# AD_1.net
KiCad netlist of a schematic drawn in Altium Designer
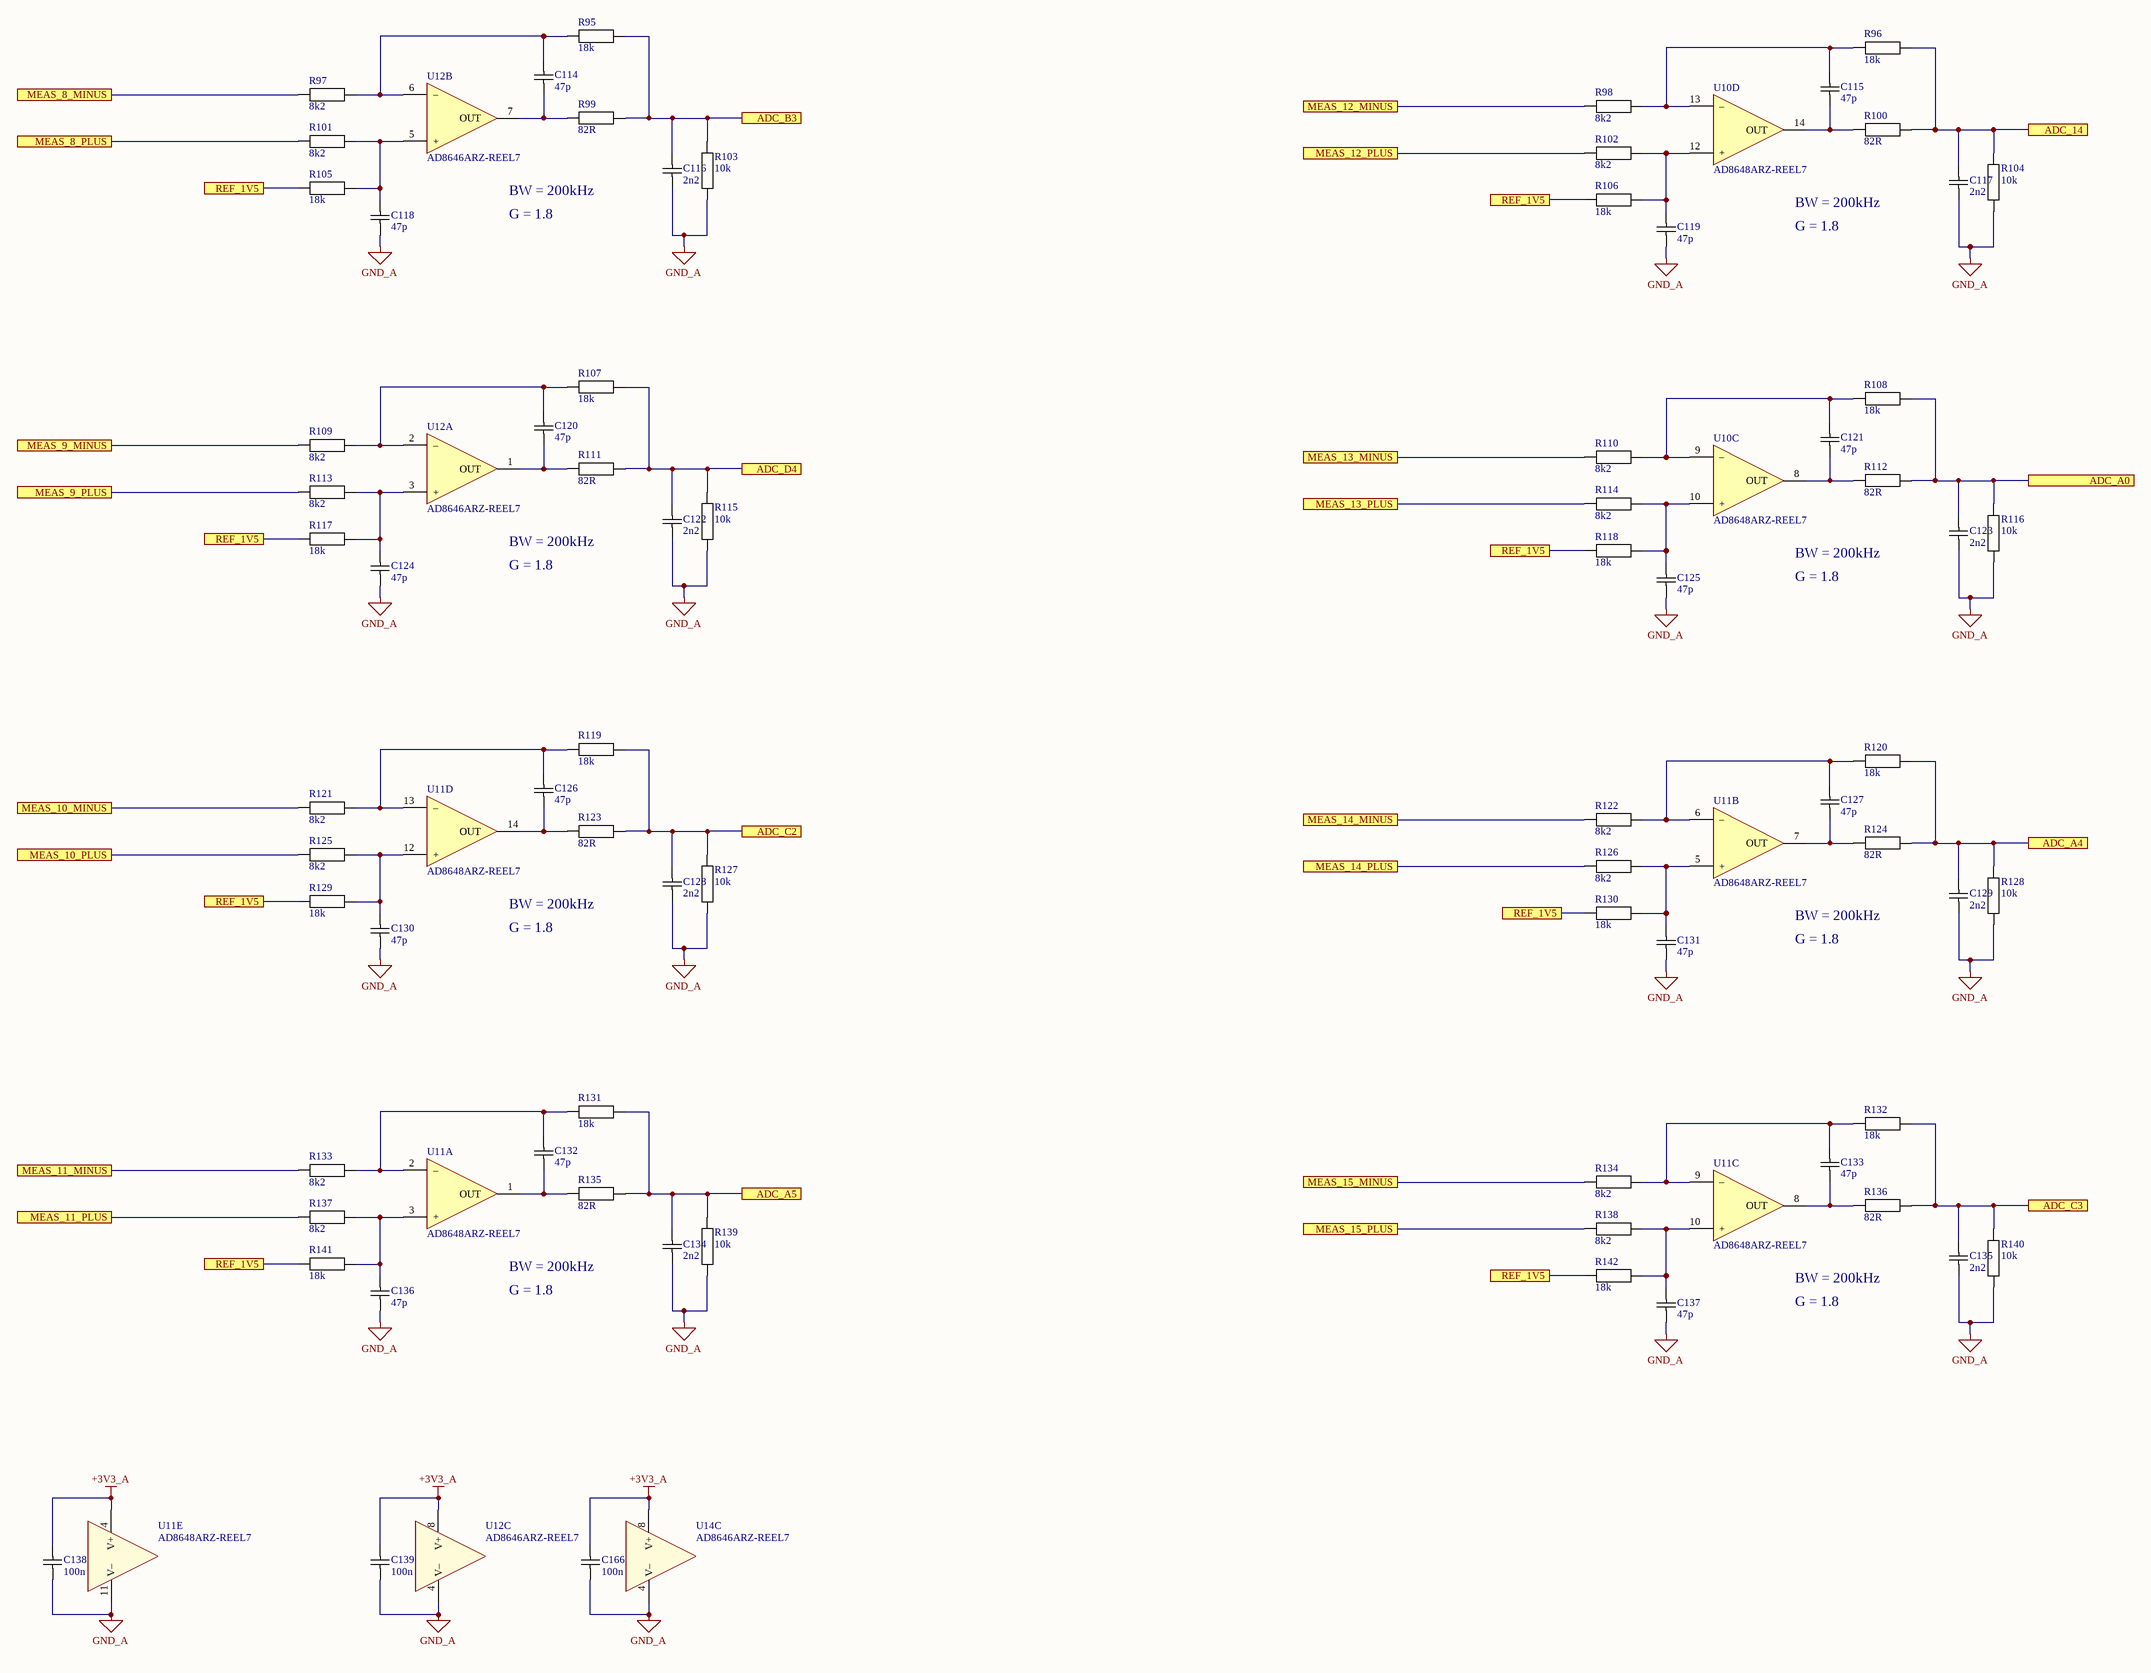
[diagram p0: AD_1.SchDoc]

(export (version "E")
  (design (tool "Eeschema 10.0.6"))
  (components
    (comp (ref "C114")
      (value "47p")
      (footprint "CAPACITOR 1608 REFLOW")
      (description "Capacitor X7R 10% 50V 1608(0603)")
      (libsource (lib "Capacitor") (part "Capacitor"))
    )
    (comp (ref "C115")
      (value "47p")
      (footprint "CAPACITOR 1608 REFLOW")
      (description "Capacitor X7R 10% 50V 1608(0603)")
      (libsource (lib "Capacitor") (part "Capacitor"))
    )
    (comp (ref "C116")
      (value "2n2")
      (footprint "CAPACITOR 1608 REFLOW")
      (description "Capacitor X7R 10% 50V 1608(0603)")
      (libsource (lib "Capacitor") (part "Capacitor"))
    )
    (comp (ref "C117")
      (value "2n2")
      (footprint "CAPACITOR 1608 REFLOW")
      (description "Capacitor X7R 10% 50V 1608(0603)")
      (libsource (lib "Capacitor") (part "Capacitor"))
    )
    (comp (ref "C118")
      (value "47p")
      (footprint "CAPACITOR 1608 REFLOW")
      (description "Capacitor X7R 10% 50V 1608(0603)")
      (libsource (lib "Capacitor") (part "Capacitor"))
    )
    (comp (ref "C119")
      (value "47p")
      (footprint "CAPACITOR 1608 REFLOW")
      (description "Capacitor X7R 10% 50V 1608(0603)")
      (libsource (lib "Capacitor") (part "Capacitor"))
    )
    (comp (ref "C120")
      (value "47p")
      (footprint "CAPACITOR 1608 REFLOW")
      (description "Capacitor X7R 10% 50V 1608(0603)")
      (libsource (lib "Capacitor") (part "Capacitor"))
    )
    (comp (ref "C121")
      (value "47p")
      (footprint "CAPACITOR 1608 REFLOW")
      (description "Capacitor X7R 10% 50V 1608(0603)")
      (libsource (lib "Capacitor") (part "Capacitor"))
    )
    (comp (ref "C122")
      (value "2n2")
      (footprint "CAPACITOR 1608 REFLOW")
      (description "Capacitor X7R 10% 50V 1608(0603)")
      (libsource (lib "Capacitor") (part "Capacitor"))
    )
    (comp (ref "C123")
      (value "2n2")
      (footprint "CAPACITOR 1608 REFLOW")
      (description "Capacitor X7R 10% 50V 1608(0603)")
      (libsource (lib "Capacitor") (part "Capacitor"))
    )
    (comp (ref "C124")
      (value "47p")
      (footprint "CAPACITOR 1608 REFLOW")
      (description "Capacitor X7R 10% 50V 1608(0603)")
      (libsource (lib "Capacitor") (part "Capacitor"))
    )
    (comp (ref "C125")
      (value "47p")
      (footprint "CAPACITOR 1608 REFLOW")
      (description "Capacitor X7R 10% 50V 1608(0603)")
      (libsource (lib "Capacitor") (part "Capacitor"))
    )
    (comp (ref "C126")
      (value "47p")
      (footprint "CAPACITOR 1608 REFLOW")
      (description "Capacitor X7R 10% 50V 1608(0603)")
      (libsource (lib "Capacitor") (part "Capacitor"))
    )
    (comp (ref "C127")
      (value "47p")
      (footprint "CAPACITOR 1608 REFLOW")
      (description "Capacitor X7R 10% 50V 1608(0603)")
      (libsource (lib "Capacitor") (part "Capacitor"))
    )
    (comp (ref "C128")
      (value "2n2")
      (footprint "CAPACITOR 1608 REFLOW")
      (description "Capacitor X7R 10% 50V 1608(0603)")
      (libsource (lib "Capacitor") (part "Capacitor"))
    )
    (comp (ref "C129")
      (value "2n2")
      (footprint "CAPACITOR 1608 REFLOW")
      (description "Capacitor X7R 10% 50V 1608(0603)")
      (libsource (lib "Capacitor") (part "Capacitor"))
    )
    (comp (ref "C130")
      (value "47p")
      (footprint "CAPACITOR 1608 REFLOW")
      (description "Capacitor X7R 10% 50V 1608(0603)")
      (libsource (lib "Capacitor") (part "Capacitor"))
    )
    (comp (ref "C131")
      (value "47p")
      (footprint "CAPACITOR 1608 REFLOW")
      (description "Capacitor X7R 10% 50V 1608(0603)")
      (libsource (lib "Capacitor") (part "Capacitor"))
    )
    (comp (ref "C132")
      (value "47p")
      (footprint "CAPACITOR 1608 REFLOW")
      (description "Capacitor X7R 10% 50V 1608(0603)")
      (libsource (lib "Capacitor") (part "Capacitor"))
    )
    (comp (ref "C133")
      (value "47p")
      (footprint "CAPACITOR 1608 REFLOW")
      (description "Capacitor X7R 10% 50V 1608(0603)")
      (libsource (lib "Capacitor") (part "Capacitor"))
    )
    (comp (ref "C134")
      (value "2n2")
      (footprint "CAPACITOR 1608 REFLOW")
      (description "Capacitor X7R 10% 50V 1608(0603)")
      (libsource (lib "Capacitor") (part "Capacitor"))
    )
    (comp (ref "C135")
      (value "2n2")
      (footprint "CAPACITOR 1608 REFLOW")
      (description "Capacitor X7R 10% 50V 1608(0603)")
      (libsource (lib "Capacitor") (part "Capacitor"))
    )
    (comp (ref "C136")
      (value "47p")
      (footprint "CAPACITOR 1608 REFLOW")
      (description "Capacitor X7R 10% 50V 1608(0603)")
      (libsource (lib "Capacitor") (part "Capacitor"))
    )
    (comp (ref "C137")
      (value "47p")
      (footprint "CAPACITOR 1608 REFLOW")
      (description "Capacitor X7R 10% 50V 1608(0603)")
      (libsource (lib "Capacitor") (part "Capacitor"))
    )
    (comp (ref "C138")
      (value "100n")
      (footprint "CAPACITOR 1608 REFLOW")
      (description "Capacitor X7R 10% 50V 1608(0603)")
      (libsource (lib "Capacitor") (part "Capacitor"))
    )
    (comp (ref "C139")
      (value "100n")
      (footprint "CAPACITOR 1608 REFLOW")
      (description "Capacitor X7R 10% 50V 1608(0603)")
      (libsource (lib "Capacitor") (part "Capacitor"))
    )
    (comp (ref "C166")
      (value "100n")
      (footprint "CAPACITOR 1608 REFLOW")
      (description "Capacitor X7R 10% 50V 1608(0603)")
      (libsource (lib "Capacitor") (part "Capacitor"))
    )
    (comp (ref "R95")
      (value "18k")
      (footprint "RESISTOR 1608 REFLOW")
      (description "Resistor 1% 50V 100mW 1608(0603)")
      (libsource (lib "Resistor") (part "Resistor"))
    )
    (comp (ref "R96")
      (value "18k")
      (footprint "RESISTOR 1608 REFLOW")
      (description "Resistor 1% 50V 100mW 1608(0603)")
      (libsource (lib "Resistor") (part "Resistor"))
    )
    (comp (ref "R97")
      (value "8k2")
      (footprint "RESISTOR 1608 REFLOW")
      (description "Resistor 1% 50V 100mW 1608(0603)")
      (libsource (lib "Resistor") (part "Resistor"))
    )
    (comp (ref "R98")
      (value "8k2")
      (footprint "RESISTOR 1608 REFLOW")
      (description "Resistor 1% 50V 100mW 1608(0603)")
      (libsource (lib "Resistor") (part "Resistor"))
    )
    (comp (ref "R99")
      (value "82R")
      (footprint "RESISTOR 1608 REFLOW")
      (description "Resistor 1% 50V 100mW 1608(0603)")
      (libsource (lib "Resistor") (part "Resistor"))
    )
    (comp (ref "R100")
      (value "82R")
      (footprint "RESISTOR 1608 REFLOW")
      (description "Resistor 1% 50V 100mW 1608(0603)")
      (libsource (lib "Resistor") (part "Resistor"))
    )
    (comp (ref "R101")
      (value "8k2")
      (footprint "RESISTOR 1608 REFLOW")
      (description "Resistor 1% 50V 100mW 1608(0603)")
      (libsource (lib "Resistor") (part "Resistor"))
    )
    (comp (ref "R102")
      (value "8k2")
      (footprint "RESISTOR 1608 REFLOW")
      (description "Resistor 1% 50V 100mW 1608(0603)")
      (libsource (lib "Resistor") (part "Resistor"))
    )
    (comp (ref "R103")
      (value "10k")
      (footprint "RESISTOR 1608 REFLOW")
      (description "Resistor 1% 50V 100mW 1608(0603)")
      (libsource (lib "Resistor") (part "Resistor"))
    )
    (comp (ref "R104")
      (value "10k")
      (footprint "RESISTOR 1608 REFLOW")
      (description "Resistor 1% 50V 100mW 1608(0603)")
      (libsource (lib "Resistor") (part "Resistor"))
    )
    (comp (ref "R105")
      (value "18k")
      (footprint "RESISTOR 1608 REFLOW")
      (description "Resistor 1% 50V 100mW 1608(0603)")
      (libsource (lib "Resistor") (part "Resistor"))
    )
    (comp (ref "R106")
      (value "18k")
      (footprint "RESISTOR 1608 REFLOW")
      (description "Resistor 1% 50V 100mW 1608(0603)")
      (libsource (lib "Resistor") (part "Resistor"))
    )
    (comp (ref "R107")
      (value "18k")
      (footprint "RESISTOR 1608 REFLOW")
      (description "Resistor 1% 50V 100mW 1608(0603)")
      (libsource (lib "Resistor") (part "Resistor"))
    )
    (comp (ref "R108")
      (value "18k")
      (footprint "RESISTOR 1608 REFLOW")
      (description "Resistor 1% 50V 100mW 1608(0603)")
      (libsource (lib "Resistor") (part "Resistor"))
    )
    (comp (ref "R109")
      (value "8k2")
      (footprint "RESISTOR 1608 REFLOW")
      (description "Resistor 1% 50V 100mW 1608(0603)")
      (libsource (lib "Resistor") (part "Resistor"))
    )
    (comp (ref "R110")
      (value "8k2")
      (footprint "RESISTOR 1608 REFLOW")
      (description "Resistor 1% 50V 100mW 1608(0603)")
      (libsource (lib "Resistor") (part "Resistor"))
    )
    (comp (ref "R111")
      (value "82R")
      (footprint "RESISTOR 1608 REFLOW")
      (description "Resistor 1% 50V 100mW 1608(0603)")
      (libsource (lib "Resistor") (part "Resistor"))
    )
    (comp (ref "R112")
      (value "82R")
      (footprint "RESISTOR 1608 REFLOW")
      (description "Resistor 1% 50V 100mW 1608(0603)")
      (libsource (lib "Resistor") (part "Resistor"))
    )
    (comp (ref "R113")
      (value "8k2")
      (footprint "RESISTOR 1608 REFLOW")
      (description "Resistor 1% 50V 100mW 1608(0603)")
      (libsource (lib "Resistor") (part "Resistor"))
    )
    (comp (ref "R114")
      (value "8k2")
      (footprint "RESISTOR 1608 REFLOW")
      (description "Resistor 1% 50V 100mW 1608(0603)")
      (libsource (lib "Resistor") (part "Resistor"))
    )
    (comp (ref "R115")
      (value "10k")
      (footprint "RESISTOR 1608 REFLOW")
      (description "Resistor 1% 50V 100mW 1608(0603)")
      (libsource (lib "Resistor") (part "Resistor"))
    )
    (comp (ref "R116")
      (value "10k")
      (footprint "RESISTOR 1608 REFLOW")
      (description "Resistor 1% 50V 100mW 1608(0603)")
      (libsource (lib "Resistor") (part "Resistor"))
    )
    (comp (ref "R117")
      (value "18k")
      (footprint "RESISTOR 1608 REFLOW")
      (description "Resistor 1% 50V 100mW 1608(0603)")
      (libsource (lib "Resistor") (part "Resistor"))
    )
    (comp (ref "R118")
      (value "18k")
      (footprint "RESISTOR 1608 REFLOW")
      (description "Resistor 1% 50V 100mW 1608(0603)")
      (libsource (lib "Resistor") (part "Resistor"))
    )
    (comp (ref "R119")
      (value "18k")
      (footprint "RESISTOR 1608 REFLOW")
      (description "Resistor 1% 50V 100mW 1608(0603)")
      (libsource (lib "Resistor") (part "Resistor"))
    )
    (comp (ref "R120")
      (value "18k")
      (footprint "RESISTOR 1608 REFLOW")
      (description "Resistor 1% 50V 100mW 1608(0603)")
      (libsource (lib "Resistor") (part "Resistor"))
    )
    (comp (ref "R121")
      (value "8k2")
      (footprint "RESISTOR 1608 REFLOW")
      (description "Resistor 1% 50V 100mW 1608(0603)")
      (libsource (lib "Resistor") (part "Resistor"))
    )
    (comp (ref "R122")
      (value "8k2")
      (footprint "RESISTOR 1608 REFLOW")
      (description "Resistor 1% 50V 100mW 1608(0603)")
      (libsource (lib "Resistor") (part "Resistor"))
    )
    (comp (ref "R123")
      (value "82R")
      (footprint "RESISTOR 1608 REFLOW")
      (description "Resistor 1% 50V 100mW 1608(0603)")
      (libsource (lib "Resistor") (part "Resistor"))
    )
    (comp (ref "R124")
      (value "82R")
      (footprint "RESISTOR 1608 REFLOW")
      (description "Resistor 1% 50V 100mW 1608(0603)")
      (libsource (lib "Resistor") (part "Resistor"))
    )
    (comp (ref "R125")
      (value "8k2")
      (footprint "RESISTOR 1608 REFLOW")
      (description "Resistor 1% 50V 100mW 1608(0603)")
      (libsource (lib "Resistor") (part "Resistor"))
    )
    (comp (ref "R126")
      (value "8k2")
      (footprint "RESISTOR 1608 REFLOW")
      (description "Resistor 1% 50V 100mW 1608(0603)")
      (libsource (lib "Resistor") (part "Resistor"))
    )
    (comp (ref "R127")
      (value "10k")
      (footprint "RESISTOR 1608 REFLOW")
      (description "Resistor 1% 50V 100mW 1608(0603)")
      (libsource (lib "Resistor") (part "Resistor"))
    )
    (comp (ref "R128")
      (value "10k")
      (footprint "RESISTOR 1608 REFLOW")
      (description "Resistor 1% 50V 100mW 1608(0603)")
      (libsource (lib "Resistor") (part "Resistor"))
    )
    (comp (ref "R129")
      (value "18k")
      (footprint "RESISTOR 1608 REFLOW")
      (description "Resistor 1% 50V 100mW 1608(0603)")
      (libsource (lib "Resistor") (part "Resistor"))
    )
    (comp (ref "R130")
      (value "18k")
      (footprint "RESISTOR 1608 REFLOW")
      (description "Resistor 1% 50V 100mW 1608(0603)")
      (libsource (lib "Resistor") (part "Resistor"))
    )
    (comp (ref "R131")
      (value "18k")
      (footprint "RESISTOR 1608 REFLOW")
      (description "Resistor 1% 50V 100mW 1608(0603)")
      (libsource (lib "Resistor") (part "Resistor"))
    )
    (comp (ref "R132")
      (value "18k")
      (footprint "RESISTOR 1608 REFLOW")
      (description "Resistor 1% 50V 100mW 1608(0603)")
      (libsource (lib "Resistor") (part "Resistor"))
    )
    (comp (ref "R133")
      (value "8k2")
      (footprint "RESISTOR 1608 REFLOW")
      (description "Resistor 1% 50V 100mW 1608(0603)")
      (libsource (lib "Resistor") (part "Resistor"))
    )
    (comp (ref "R134")
      (value "8k2")
      (footprint "RESISTOR 1608 REFLOW")
      (description "Resistor 1% 50V 100mW 1608(0603)")
      (libsource (lib "Resistor") (part "Resistor"))
    )
    (comp (ref "R135")
      (value "82R")
      (footprint "RESISTOR 1608 REFLOW")
      (description "Resistor 1% 50V 100mW 1608(0603)")
      (libsource (lib "Resistor") (part "Resistor"))
    )
    (comp (ref "R136")
      (value "82R")
      (footprint "RESISTOR 1608 REFLOW")
      (description "Resistor 1% 50V 100mW 1608(0603)")
      (libsource (lib "Resistor") (part "Resistor"))
    )
    (comp (ref "R137")
      (value "8k2")
      (footprint "RESISTOR 1608 REFLOW")
      (description "Resistor 1% 50V 100mW 1608(0603)")
      (libsource (lib "Resistor") (part "Resistor"))
    )
    (comp (ref "R138")
      (value "8k2")
      (footprint "RESISTOR 1608 REFLOW")
      (description "Resistor 1% 50V 100mW 1608(0603)")
      (libsource (lib "Resistor") (part "Resistor"))
    )
    (comp (ref "R139")
      (value "10k")
      (footprint "RESISTOR 1608 REFLOW")
      (description "Resistor 1% 50V 100mW 1608(0603)")
      (libsource (lib "Resistor") (part "Resistor"))
    )
    (comp (ref "R140")
      (value "10k")
      (footprint "RESISTOR 1608 REFLOW")
      (description "Resistor 1% 50V 100mW 1608(0603)")
      (libsource (lib "Resistor") (part "Resistor"))
    )
    (comp (ref "R141")
      (value "18k")
      (footprint "RESISTOR 1608 REFLOW")
      (description "Resistor 1% 50V 100mW 1608(0603)")
      (libsource (lib "Resistor") (part "Resistor"))
    )
    (comp (ref "R142")
      (value "18k")
      (footprint "RESISTOR 1608 REFLOW")
      (description "Resistor 1% 50V 100mW 1608(0603)")
      (libsource (lib "Resistor") (part "Resistor"))
    )
    (comp (ref "U10")
      (value "AD8648ARZ-REEL7")
      (footprint "SO14 P1.27 C4.0X8.8 H1.75")
      (description "Generic quad OPA 14 pins")
      (fields (field (name "MANUFACTURER") "Analog Devices"))
      (libsource (lib "Amplifier") (part "OPA QUAD"))
    )
    (comp (ref "U11")
      (value "AD8648ARZ-REEL7")
      (footprint "SO14 P1.27 C4.0X8.8 H1.75")
      (description "Generic quad OPA 14 pins")
      (fields (field (name "MANUFACTURER") "Analog Devices"))
      (libsource (lib "Amplifier") (part "OPA QUAD"))
    )
    (comp (ref "U12")
      (value "AD8646ARZ-REEL7")
      (footprint "SO8 P1.27 C4.0X5.0 H1.75")
      (description "Generic dual OPA 8 pins")
      (fields (field (name "MANUFACTURER") "Analog Devices"))
      (libsource (lib "Amplifier") (part "OPA DUAL"))
    )
    (comp (ref "U14")
      (value "AD8646ARZ-REEL7")
      (footprint "SO8 P1.27 C4.0X5.0 H1.75")
      (description "Generic dual OPA 8 pins")
      (fields (field (name "MANUFACTURER") "Analog Devices"))
      (libsource (lib "Amplifier") (part "OPA DUAL"))
    )
  )
  (nets
    (net (code "1") (name "+3V3_A") (class "Default")
      (node (ref "C138") (pin "2") (pinfunction "2_2") (pintype "passive"))
      (node (ref "C139") (pin "2") (pinfunction "2_2") (pintype "passive"))
      (node (ref "C166") (pin "2") (pinfunction "2_2") (pintype "passive"))
      (node (ref "U11") (pin "4") (pinfunction "V+_4") (pintype "passive"))
      (node (ref "U12") (pin "8") (pinfunction "V+_8") (pintype "passive"))
      (node (ref "U14") (pin "8") (pinfunction "V+_8") (pintype "passive"))
    )
    (net (code "2") (name "/ADC_14") (class "Default")
      (node (ref "C117") (pin "2") (pinfunction "2_2") (pintype "passive"))
      (node (ref "R100") (pin "2") (pinfunction "2_2") (pintype "passive"))
      (node (ref "R104") (pin "1") (pinfunction "1_1") (pintype "passive"))
      (node (ref "R96") (pin "2") (pinfunction "2_2") (pintype "passive"))
    )
    (net (code "3") (name "/ADC_A0") (class "Default")
      (node (ref "C123") (pin "2") (pinfunction "2_2") (pintype "passive"))
      (node (ref "R108") (pin "2") (pinfunction "2_2") (pintype "passive"))
      (node (ref "R112") (pin "2") (pinfunction "2_2") (pintype "passive"))
      (node (ref "R116") (pin "1") (pinfunction "1_1") (pintype "passive"))
    )
    (net (code "4") (name "/ADC_A4") (class "Default")
      (node (ref "C129") (pin "2") (pinfunction "2_2") (pintype "passive"))
      (node (ref "R120") (pin "2") (pinfunction "2_2") (pintype "passive"))
      (node (ref "R124") (pin "2") (pinfunction "2_2") (pintype "passive"))
      (node (ref "R128") (pin "1") (pinfunction "1_1") (pintype "passive"))
    )
    (net (code "5") (name "/ADC_A5") (class "Default")
      (node (ref "C134") (pin "2") (pinfunction "2_2") (pintype "passive"))
      (node (ref "R131") (pin "2") (pinfunction "2_2") (pintype "passive"))
      (node (ref "R135") (pin "2") (pinfunction "2_2") (pintype "passive"))
      (node (ref "R139") (pin "1") (pinfunction "1_1") (pintype "passive"))
    )
    (net (code "6") (name "/ADC_B3") (class "Default")
      (node (ref "C116") (pin "2") (pinfunction "2_2") (pintype "passive"))
      (node (ref "R103") (pin "1") (pinfunction "1_1") (pintype "passive"))
      (node (ref "R95") (pin "2") (pinfunction "2_2") (pintype "passive"))
      (node (ref "R99") (pin "2") (pinfunction "2_2") (pintype "passive"))
    )
    (net (code "7") (name "/ADC_C2") (class "Default")
      (node (ref "C128") (pin "2") (pinfunction "2_2") (pintype "passive"))
      (node (ref "R119") (pin "2") (pinfunction "2_2") (pintype "passive"))
      (node (ref "R123") (pin "2") (pinfunction "2_2") (pintype "passive"))
      (node (ref "R127") (pin "1") (pinfunction "1_1") (pintype "passive"))
    )
    (net (code "8") (name "/ADC_C3") (class "Default")
      (node (ref "C135") (pin "2") (pinfunction "2_2") (pintype "passive"))
      (node (ref "R132") (pin "2") (pinfunction "2_2") (pintype "passive"))
      (node (ref "R136") (pin "2") (pinfunction "2_2") (pintype "passive"))
      (node (ref "R140") (pin "1") (pinfunction "1_1") (pintype "passive"))
    )
    (net (code "9") (name "/ADC_D4") (class "Default")
      (node (ref "C122") (pin "2") (pinfunction "2_2") (pintype "passive"))
      (node (ref "R107") (pin "2") (pinfunction "2_2") (pintype "passive"))
      (node (ref "R111") (pin "2") (pinfunction "2_2") (pintype "passive"))
      (node (ref "R115") (pin "1") (pinfunction "1_1") (pintype "passive"))
    )
    (net (code "10") (name "/MEAS_8_MINUS") (class "Default")
      (node (ref "R97") (pin "1") (pinfunction "1_1") (pintype "passive"))
    )
    (net (code "11") (name "/MEAS_8_PLUS") (class "Default")
      (node (ref "R101") (pin "1") (pinfunction "1_1") (pintype "passive"))
    )
    (net (code "12") (name "/MEAS_9_MINUS") (class "Default")
      (node (ref "R109") (pin "1") (pinfunction "1_1") (pintype "passive"))
    )
    (net (code "13") (name "/MEAS_9_PLUS") (class "Default")
      (node (ref "R113") (pin "1") (pinfunction "1_1") (pintype "passive"))
    )
    (net (code "14") (name "/MEAS_10_MINUS") (class "Default")
      (node (ref "R121") (pin "1") (pinfunction "1_1") (pintype "passive"))
    )
    (net (code "15") (name "/MEAS_10_PLUS") (class "Default")
      (node (ref "R125") (pin "1") (pinfunction "1_1") (pintype "passive"))
    )
    (net (code "16") (name "/MEAS_11_MINUS") (class "Default")
      (node (ref "R133") (pin "1") (pinfunction "1_1") (pintype "passive"))
    )
    (net (code "17") (name "/MEAS_11_PLUS") (class "Default")
      (node (ref "R137") (pin "1") (pinfunction "1_1") (pintype "passive"))
    )
    (net (code "18") (name "/MEAS_12_MINUS") (class "Default")
      (node (ref "R98") (pin "1") (pinfunction "1_1") (pintype "passive"))
    )
    (net (code "19") (name "/MEAS_12_PLUS") (class "Default")
      (node (ref "R102") (pin "1") (pinfunction "1_1") (pintype "passive"))
    )
    (net (code "20") (name "/MEAS_13_MINUS") (class "Default")
      (node (ref "R110") (pin "1") (pinfunction "1_1") (pintype "passive"))
    )
    (net (code "21") (name "/MEAS_13_PLUS") (class "Default")
      (node (ref "R114") (pin "1") (pinfunction "1_1") (pintype "passive"))
    )
    (net (code "22") (name "/MEAS_14_MINUS") (class "Default")
      (node (ref "R122") (pin "1") (pinfunction "1_1") (pintype "passive"))
    )
    (net (code "23") (name "/MEAS_14_PLUS") (class "Default")
      (node (ref "R126") (pin "1") (pinfunction "1_1") (pintype "passive"))
    )
    (net (code "24") (name "/MEAS_15_MINUS") (class "Default")
      (node (ref "R134") (pin "1") (pinfunction "1_1") (pintype "passive"))
    )
    (net (code "25") (name "/MEAS_15_PLUS") (class "Default")
      (node (ref "R138") (pin "1") (pinfunction "1_1") (pintype "passive"))
    )
    (net (code "26") (name "/REF_1V5") (class "Default")
      (node (ref "R105") (pin "2") (pinfunction "2_2") (pintype "passive"))
      (node (ref "R106") (pin "2") (pinfunction "2_2") (pintype "passive"))
      (node (ref "R117") (pin "2") (pinfunction "2_2") (pintype "passive"))
      (node (ref "R118") (pin "2") (pinfunction "2_2") (pintype "passive"))
      (node (ref "R129") (pin "2") (pinfunction "2_2") (pintype "passive"))
      (node (ref "R130") (pin "2") (pinfunction "2_2") (pintype "passive"))
      (node (ref "R141") (pin "2") (pinfunction "2_2") (pintype "passive"))
      (node (ref "R142") (pin "2") (pinfunction "2_2") (pintype "passive"))
    )
    (net (code "27") (name "GND_A") (class "Default")
      (node (ref "C116") (pin "1") (pinfunction "1_1") (pintype "passive"))
      (node (ref "C117") (pin "1") (pinfunction "1_1") (pintype "passive"))
      (node (ref "C118") (pin "1") (pinfunction "1_1") (pintype "passive"))
      (node (ref "C119") (pin "1") (pinfunction "1_1") (pintype "passive"))
      (node (ref "C122") (pin "1") (pinfunction "1_1") (pintype "passive"))
      (node (ref "C123") (pin "1") (pinfunction "1_1") (pintype "passive"))
      (node (ref "C124") (pin "1") (pinfunction "1_1") (pintype "passive"))
      (node (ref "C125") (pin "1") (pinfunction "1_1") (pintype "passive"))
      (node (ref "C128") (pin "1") (pinfunction "1_1") (pintype "passive"))
      (node (ref "C129") (pin "1") (pinfunction "1_1") (pintype "passive"))
      (node (ref "C130") (pin "1") (pinfunction "1_1") (pintype "passive"))
      (node (ref "C131") (pin "1") (pinfunction "1_1") (pintype "passive"))
      (node (ref "C134") (pin "1") (pinfunction "1_1") (pintype "passive"))
      (node (ref "C135") (pin "1") (pinfunction "1_1") (pintype "passive"))
      (node (ref "C136") (pin "1") (pinfunction "1_1") (pintype "passive"))
      (node (ref "C137") (pin "1") (pinfunction "1_1") (pintype "passive"))
      (node (ref "C138") (pin "1") (pinfunction "1_1") (pintype "passive"))
      (node (ref "C139") (pin "1") (pinfunction "1_1") (pintype "passive"))
      (node (ref "C166") (pin "1") (pinfunction "1_1") (pintype "passive"))
      (node (ref "R103") (pin "2") (pinfunction "2_2") (pintype "passive"))
      (node (ref "R104") (pin "2") (pinfunction "2_2") (pintype "passive"))
      (node (ref "R115") (pin "2") (pinfunction "2_2") (pintype "passive"))
      (node (ref "R116") (pin "2") (pinfunction "2_2") (pintype "passive"))
      (node (ref "R127") (pin "2") (pinfunction "2_2") (pintype "passive"))
      (node (ref "R128") (pin "2") (pinfunction "2_2") (pintype "passive"))
      (node (ref "R139") (pin "2") (pinfunction "2_2") (pintype "passive"))
      (node (ref "R140") (pin "2") (pinfunction "2_2") (pintype "passive"))
      (node (ref "U11") (pin "11") (pinfunction "V–_11") (pintype "passive"))
      (node (ref "U12") (pin "4") (pinfunction "V–_4") (pintype "passive"))
      (node (ref "U14") (pin "4") (pinfunction "V–_4") (pintype "passive"))
    )
    (net (code "28") (name "Net-(U10C-+)") (class "Default")
      (node (ref "C125") (pin "2") (pinfunction "2_2") (pintype "passive"))
      (node (ref "R114") (pin "2") (pinfunction "2_2") (pintype "passive"))
      (node (ref "R118") (pin "1") (pinfunction "1_1") (pintype "passive"))
      (node (ref "U10") (pin "10") (pinfunction "+_10") (pintype "passive"))
    )
    (net (code "29") (name "Net-(U10C-OUT)") (class "Default")
      (node (ref "C121") (pin "1") (pinfunction "1_1") (pintype "passive"))
      (node (ref "R112") (pin "1") (pinfunction "1_1") (pintype "passive"))
      (node (ref "U10") (pin "8") (pinfunction "OUT_8") (pintype "passive"))
    )
    (net (code "30") (name "Net-(U10C-–)") (class "Default")
      (node (ref "C121") (pin "2") (pinfunction "2_2") (pintype "passive"))
      (node (ref "R108") (pin "1") (pinfunction "1_1") (pintype "passive"))
      (node (ref "R110") (pin "2") (pinfunction "2_2") (pintype "passive"))
      (node (ref "U10") (pin "9") (pinfunction "–_9") (pintype "passive"))
    )
    (net (code "31") (name "Net-(U10D-+)") (class "Default")
      (node (ref "C119") (pin "2") (pinfunction "2_2") (pintype "passive"))
      (node (ref "R102") (pin "2") (pinfunction "2_2") (pintype "passive"))
      (node (ref "R106") (pin "1") (pinfunction "1_1") (pintype "passive"))
      (node (ref "U10") (pin "12") (pinfunction "+_12") (pintype "passive"))
    )
    (net (code "32") (name "Net-(U10D-OUT)") (class "Default")
      (node (ref "C115") (pin "1") (pinfunction "1_1") (pintype "passive"))
      (node (ref "R100") (pin "1") (pinfunction "1_1") (pintype "passive"))
      (node (ref "U10") (pin "14") (pinfunction "OUT_14") (pintype "passive"))
    )
    (net (code "33") (name "Net-(U10D-–)") (class "Default")
      (node (ref "C115") (pin "2") (pinfunction "2_2") (pintype "passive"))
      (node (ref "R96") (pin "1") (pinfunction "1_1") (pintype "passive"))
      (node (ref "R98") (pin "2") (pinfunction "2_2") (pintype "passive"))
      (node (ref "U10") (pin "13") (pinfunction "–_13") (pintype "passive"))
    )
    (net (code "34") (name "Net-(U11A-+)") (class "Default")
      (node (ref "C136") (pin "2") (pinfunction "2_2") (pintype "passive"))
      (node (ref "R137") (pin "2") (pinfunction "2_2") (pintype "passive"))
      (node (ref "R141") (pin "1") (pinfunction "1_1") (pintype "passive"))
      (node (ref "U11") (pin "3") (pinfunction "+_3") (pintype "passive"))
    )
    (net (code "35") (name "Net-(U11A-OUT)") (class "Default")
      (node (ref "C132") (pin "1") (pinfunction "1_1") (pintype "passive"))
      (node (ref "R135") (pin "1") (pinfunction "1_1") (pintype "passive"))
      (node (ref "U11") (pin "1") (pinfunction "OUT_1") (pintype "passive"))
    )
    (net (code "36") (name "Net-(U11A-–)") (class "Default")
      (node (ref "C132") (pin "2") (pinfunction "2_2") (pintype "passive"))
      (node (ref "R131") (pin "1") (pinfunction "1_1") (pintype "passive"))
      (node (ref "R133") (pin "2") (pinfunction "2_2") (pintype "passive"))
      (node (ref "U11") (pin "2") (pinfunction "–_2") (pintype "passive"))
    )
    (net (code "37") (name "Net-(U11B-+)") (class "Default")
      (node (ref "C131") (pin "2") (pinfunction "2_2") (pintype "passive"))
      (node (ref "R126") (pin "2") (pinfunction "2_2") (pintype "passive"))
      (node (ref "R130") (pin "1") (pinfunction "1_1") (pintype "passive"))
      (node (ref "U11") (pin "5") (pinfunction "+_5") (pintype "passive"))
    )
    (net (code "38") (name "Net-(U11B-OUT)") (class "Default")
      (node (ref "C127") (pin "1") (pinfunction "1_1") (pintype "passive"))
      (node (ref "R124") (pin "1") (pinfunction "1_1") (pintype "passive"))
      (node (ref "U11") (pin "7") (pinfunction "OUT_7") (pintype "passive"))
    )
    (net (code "39") (name "Net-(U11B-–)") (class "Default")
      (node (ref "C127") (pin "2") (pinfunction "2_2") (pintype "passive"))
      (node (ref "R120") (pin "1") (pinfunction "1_1") (pintype "passive"))
      (node (ref "R122") (pin "2") (pinfunction "2_2") (pintype "passive"))
      (node (ref "U11") (pin "6") (pinfunction "–_6") (pintype "passive"))
    )
    (net (code "40") (name "Net-(U11C-+)") (class "Default")
      (node (ref "C137") (pin "2") (pinfunction "2_2") (pintype "passive"))
      (node (ref "R138") (pin "2") (pinfunction "2_2") (pintype "passive"))
      (node (ref "R142") (pin "1") (pinfunction "1_1") (pintype "passive"))
      (node (ref "U11") (pin "10") (pinfunction "+_10") (pintype "passive"))
    )
    (net (code "41") (name "Net-(U11C-OUT)") (class "Default")
      (node (ref "C133") (pin "1") (pinfunction "1_1") (pintype "passive"))
      (node (ref "R136") (pin "1") (pinfunction "1_1") (pintype "passive"))
      (node (ref "U11") (pin "8") (pinfunction "OUT_8") (pintype "passive"))
    )
    (net (code "42") (name "Net-(U11C-–)") (class "Default")
      (node (ref "C133") (pin "2") (pinfunction "2_2") (pintype "passive"))
      (node (ref "R132") (pin "1") (pinfunction "1_1") (pintype "passive"))
      (node (ref "R134") (pin "2") (pinfunction "2_2") (pintype "passive"))
      (node (ref "U11") (pin "9") (pinfunction "–_9") (pintype "passive"))
    )
    (net (code "43") (name "Net-(U11D-+)") (class "Default")
      (node (ref "C130") (pin "2") (pinfunction "2_2") (pintype "passive"))
      (node (ref "R125") (pin "2") (pinfunction "2_2") (pintype "passive"))
      (node (ref "R129") (pin "1") (pinfunction "1_1") (pintype "passive"))
      (node (ref "U11") (pin "12") (pinfunction "+_12") (pintype "passive"))
    )
    (net (code "44") (name "Net-(U11D-OUT)") (class "Default")
      (node (ref "C126") (pin "1") (pinfunction "1_1") (pintype "passive"))
      (node (ref "R123") (pin "1") (pinfunction "1_1") (pintype "passive"))
      (node (ref "U11") (pin "14") (pinfunction "OUT_14") (pintype "passive"))
    )
    (net (code "45") (name "Net-(U11D-–)") (class "Default")
      (node (ref "C126") (pin "2") (pinfunction "2_2") (pintype "passive"))
      (node (ref "R119") (pin "1") (pinfunction "1_1") (pintype "passive"))
      (node (ref "R121") (pin "2") (pinfunction "2_2") (pintype "passive"))
      (node (ref "U11") (pin "13") (pinfunction "–_13") (pintype "passive"))
    )
    (net (code "46") (name "Net-(U12A-+)") (class "Default")
      (node (ref "C124") (pin "2") (pinfunction "2_2") (pintype "passive"))
      (node (ref "R113") (pin "2") (pinfunction "2_2") (pintype "passive"))
      (node (ref "R117") (pin "1") (pinfunction "1_1") (pintype "passive"))
      (node (ref "U12") (pin "3") (pinfunction "+_3") (pintype "passive"))
    )
    (net (code "47") (name "Net-(U12A-OUT)") (class "Default")
      (node (ref "C120") (pin "1") (pinfunction "1_1") (pintype "passive"))
      (node (ref "R111") (pin "1") (pinfunction "1_1") (pintype "passive"))
      (node (ref "U12") (pin "1") (pinfunction "OUT_1") (pintype "passive"))
    )
    (net (code "48") (name "Net-(U12A-–)") (class "Default")
      (node (ref "C120") (pin "2") (pinfunction "2_2") (pintype "passive"))
      (node (ref "R107") (pin "1") (pinfunction "1_1") (pintype "passive"))
      (node (ref "R109") (pin "2") (pinfunction "2_2") (pintype "passive"))
      (node (ref "U12") (pin "2") (pinfunction "–_2") (pintype "passive"))
    )
    (net (code "49") (name "Net-(U12B-+)") (class "Default")
      (node (ref "C118") (pin "2") (pinfunction "2_2") (pintype "passive"))
      (node (ref "R101") (pin "2") (pinfunction "2_2") (pintype "passive"))
      (node (ref "R105") (pin "1") (pinfunction "1_1") (pintype "passive"))
      (node (ref "U12") (pin "5") (pinfunction "+_5") (pintype "passive"))
    )
    (net (code "50") (name "Net-(U12B-OUT)") (class "Default")
      (node (ref "C114") (pin "1") (pinfunction "1_1") (pintype "passive"))
      (node (ref "R99") (pin "1") (pinfunction "1_1") (pintype "passive"))
      (node (ref "U12") (pin "7") (pinfunction "OUT_7") (pintype "passive"))
    )
    (net (code "51") (name "Net-(U12B-–)") (class "Default")
      (node (ref "C114") (pin "2") (pinfunction "2_2") (pintype "passive"))
      (node (ref "R95") (pin "1") (pinfunction "1_1") (pintype "passive"))
      (node (ref "R97") (pin "2") (pinfunction "2_2") (pintype "passive"))
      (node (ref "U12") (pin "6") (pinfunction "–_6") (pintype "passive"))
    )
  )
)
